# 23_MOUNTING_HOLE.net
KiCad netlist of a schematic drawn in Altium Designer
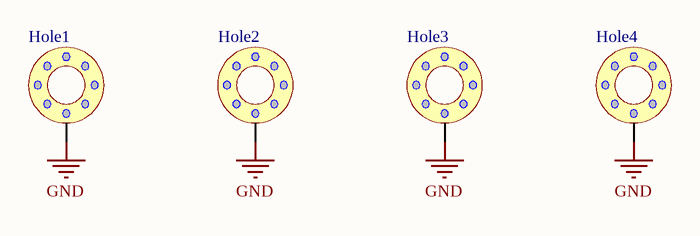
[diagram p0: 23_MOUNTING_HOLE.SchDoc]

(export (version "E")
  (design (tool "Eeschema 10.0.6"))
  (components
    (comp (ref "Hole1")
      (value "hole_space")
      (footprint "HEX-M3_NoVia")
      (libsource (lib "BEE-DAL_EXP_sche") (part "hole_space"))
    )
    (comp (ref "Hole2")
      (value "hole_space")
      (footprint "HEX-M3_NoVia")
      (libsource (lib "BEE-DAL_EXP_sche") (part "hole_space"))
    )
    (comp (ref "Hole3")
      (value "hole_space")
      (footprint "HEX-M3_NoVia")
      (libsource (lib "BEE-DAL_EXP_sche") (part "hole_space"))
    )
    (comp (ref "Hole4")
      (value "hole_space")
      (footprint "HEX-M3_NoVia")
      (libsource (lib "BEE-DAL_EXP_sche") (part "hole_space"))
    )
  )
  (nets
    (net (code "1") (name "GND") (class "Default")
      (node (ref "Hole1") (pin "1") (pinfunction "1_1") (pintype "passive"))
      (node (ref "Hole2") (pin "1") (pinfunction "1_1") (pintype "passive"))
      (node (ref "Hole3") (pin "1") (pinfunction "1_1") (pintype "passive"))
      (node (ref "Hole4") (pin "1") (pinfunction "1_1") (pintype "passive"))
    )
  )
)
